# tester.net
KiCad netlist of a schematic drawn in EAGLE
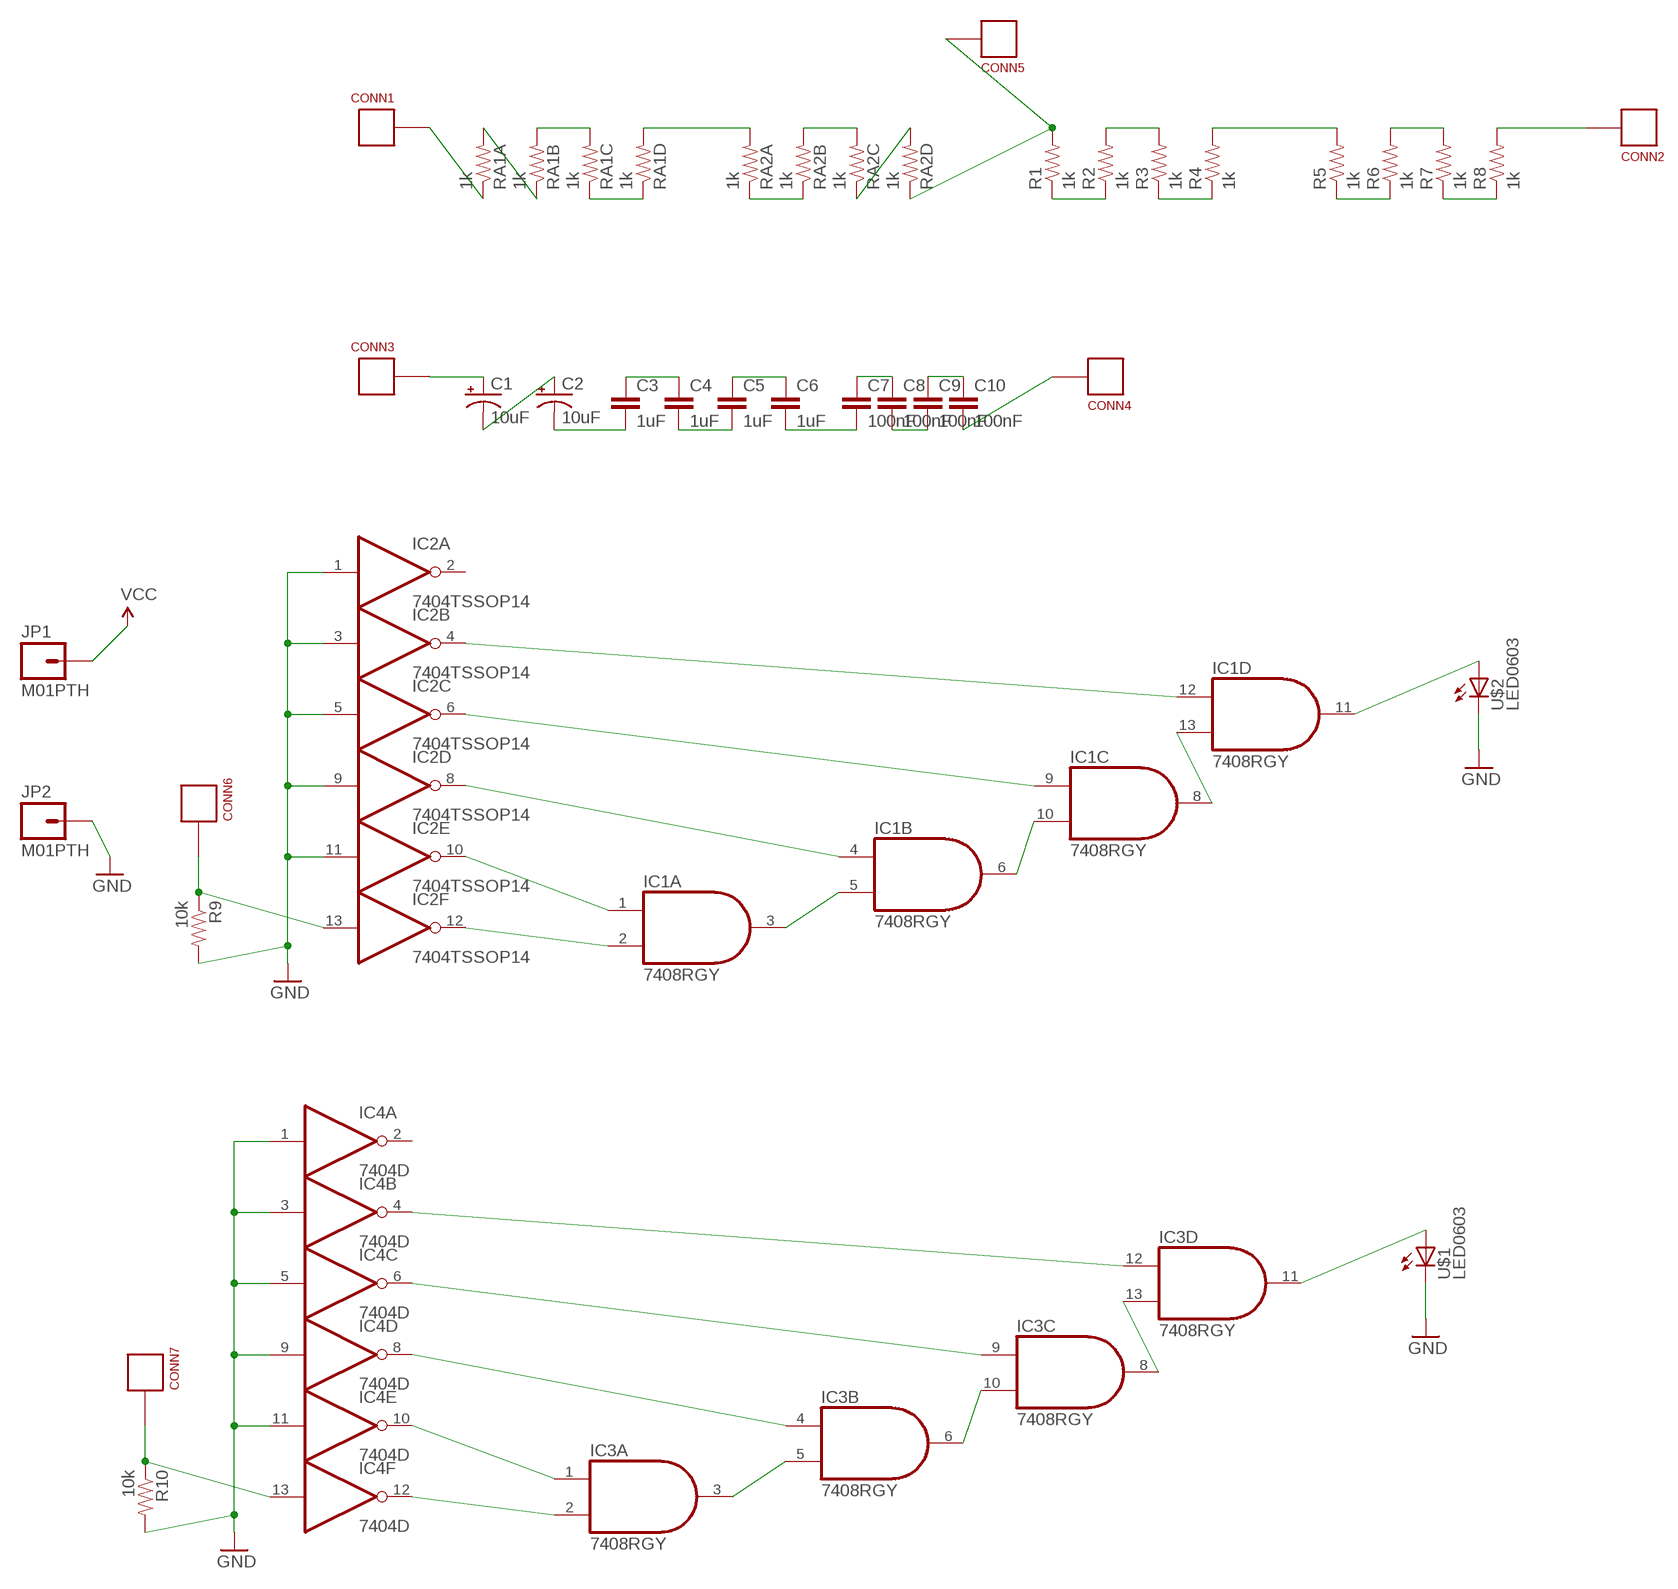
[diagram p0: schematic, sheet 1]

(export (version "E")
  (design (tool "Eeschema 10.0.6"))
  (components
    (comp (ref "C1")
      (value "10uF")
      (footprint "eagle-import:EIA3216")
      (libsource (lib "eagle-import") (part "CAP_POL1206"))
    )
    (comp (ref "C2")
      (value "10uF")
      (footprint "eagle-import:EIA3216")
      (libsource (lib "eagle-import") (part "CAP_POL1206"))
    )
    (comp (ref "C3")
      (value "1uF")
      (footprint "eagle-import:0805")
      (libsource (lib "eagle-import") (part "CAP0805"))
    )
    (comp (ref "C4")
      (value "1uF")
      (footprint "eagle-import:0805")
      (libsource (lib "eagle-import") (part "CAP0805"))
    )
    (comp (ref "C5")
      (value "1uF")
      (footprint "eagle-import:0805")
      (libsource (lib "eagle-import") (part "CAP0805"))
    )
    (comp (ref "C6")
      (value "1uF")
      (footprint "eagle-import:0805")
      (libsource (lib "eagle-import") (part "CAP0805"))
    )
    (comp (ref "C7")
      (value "100nF")
      (footprint "eagle-import:0402-CAP")
      (libsource (lib "eagle-import") (part "CAP0402-CAP"))
    )
    (comp (ref "C8")
      (value "100nF")
      (footprint "eagle-import:0402-CAP")
      (libsource (lib "eagle-import") (part "CAP0402-CAP"))
    )
    (comp (ref "C9")
      (value "100nF")
      (footprint "eagle-import:0402-CAP")
      (libsource (lib "eagle-import") (part "CAP0402-CAP"))
    )
    (comp (ref "C10")
      (value "100nF")
      (footprint "eagle-import:0402-CAP")
      (libsource (lib "eagle-import") (part "CAP0402-CAP"))
    )
    (comp (ref "CONN1")
      (value "CONNECTOR")
      (footprint "eagle-import:TESTPAD")
      (libsource (lib "eagle-import") (part "CONNECTOR"))
    )
    (comp (ref "CONN2")
      (value "CONNECTOR")
      (footprint "eagle-import:TESTPAD")
      (libsource (lib "eagle-import") (part "CONNECTOR"))
    )
    (comp (ref "CONN3")
      (value "CONNECTOR")
      (footprint "eagle-import:TESTPAD")
      (libsource (lib "eagle-import") (part "CONNECTOR"))
    )
    (comp (ref "CONN4")
      (value "CONNECTOR")
      (footprint "eagle-import:TESTPAD")
      (libsource (lib "eagle-import") (part "CONNECTOR"))
    )
    (comp (ref "CONN5")
      (value "CONNECTOR")
      (footprint "eagle-import:TESTPAD")
      (libsource (lib "eagle-import") (part "CONNECTOR"))
    )
    (comp (ref "CONN6")
      (value "CONNECTOR")
      (footprint "eagle-import:TESTPAD")
      (libsource (lib "eagle-import") (part "CONNECTOR"))
    )
    (comp (ref "CONN7")
      (value "CONNECTOR")
      (footprint "eagle-import:TESTPAD")
      (libsource (lib "eagle-import") (part "CONNECTOR"))
    )
    (comp (ref "IC1")
      (value "7408RGY")
      (footprint "eagle-import:QFN14")
      (libsource (lib "eagle-import") (part "7408RGY"))
    )
    (comp (ref "IC2")
      (value "7404TSSOP14")
      (footprint "eagle-import:TSSOP14")
      (libsource (lib "eagle-import") (part "7404TSSOP14"))
    )
    (comp (ref "IC3")
      (value "7408RGY")
      (footprint "eagle-import:QFN14")
      (libsource (lib "eagle-import") (part "7408RGY"))
    )
    (comp (ref "IC4")
      (value "7404D")
      (footprint "eagle-import:SO14")
      (libsource (lib "eagle-import") (part "7404D"))
    )
    (comp (ref "JP1")
      (value "M01PTH")
      (footprint "eagle-import:1X01")
      (libsource (lib "eagle-import") (part "M01PTH"))
    )
    (comp (ref "JP2")
      (value "M01PTH")
      (footprint "eagle-import:1X01")
      (libsource (lib "eagle-import") (part "M01PTH"))
    )
    (comp (ref "R1")
      (value "1k")
      (footprint "eagle-import:0603-RES")
      (libsource (lib "eagle-import") (part "RESISTOR0603"))
    )
    (comp (ref "R2")
      (value "1k")
      (footprint "eagle-import:0603-RES")
      (libsource (lib "eagle-import") (part "RESISTOR0603"))
    )
    (comp (ref "R3")
      (value "1k")
      (footprint "eagle-import:0603-RES")
      (libsource (lib "eagle-import") (part "RESISTOR0603"))
    )
    (comp (ref "R4")
      (value "1k")
      (footprint "eagle-import:0603-RES")
      (libsource (lib "eagle-import") (part "RESISTOR0603"))
    )
    (comp (ref "R5")
      (value "1k")
      (footprint "eagle-import:0402-RES")
      (libsource (lib "eagle-import") (part "RESISTOR0402"))
    )
    (comp (ref "R6")
      (value "1k")
      (footprint "eagle-import:0402-RES")
      (libsource (lib "eagle-import") (part "RESISTOR0402"))
    )
    (comp (ref "R7")
      (value "1k")
      (footprint "eagle-import:0402-RES")
      (libsource (lib "eagle-import") (part "RESISTOR0402"))
    )
    (comp (ref "R8")
      (value "1k")
      (footprint "eagle-import:0402-RES")
      (libsource (lib "eagle-import") (part "RESISTOR0402"))
    )
    (comp (ref "R9")
      (value "10k")
      (footprint "eagle-import:0402-RES")
      (libsource (lib "eagle-import") (part "RESISTOR0402"))
    )
    (comp (ref "R10")
      (value "10k")
      (footprint "eagle-import:0402-RES")
      (libsource (lib "eagle-import") (part "RESISTOR0402"))
    )
    (comp (ref "RA1")
      (value "1k")
      (footprint "eagle-import:0603-ARV")
      (libsource (lib "eagle-import") (part "RESISTOR_ARRAY0603_X4"))
    )
    (comp (ref "RA2")
      (value "1k")
      (footprint "eagle-import:0603-ARV")
      (libsource (lib "eagle-import") (part "RESISTOR_ARRAY0603_X4"))
    )
    (comp (ref "U$1")
      (value "LED0603")
      (footprint "eagle-import:0603_LED")
      (libsource (lib "eagle-import") (part "LED0603"))
    )
    (comp (ref "U$2")
      (value "LED0603")
      (footprint "eagle-import:0603_LED")
      (libsource (lib "eagle-import") (part "LED0603"))
    )
  )
  (nets
    (net (code "1") (name "GND") (class "Default")
      (node (ref "IC2") (pin "1") (pinfunction "I_1") (pintype "input"))
      (node (ref "IC2") (pin "11") (pinfunction "I_11") (pintype "input"))
      (node (ref "IC2") (pin "3") (pinfunction "I_3") (pintype "input"))
      (node (ref "IC2") (pin "5") (pinfunction "I_5") (pintype "input"))
      (node (ref "IC2") (pin "9") (pinfunction "I_9") (pintype "input"))
      (node (ref "IC4") (pin "1") (pinfunction "I_1") (pintype "input"))
      (node (ref "IC4") (pin "11") (pinfunction "I_11") (pintype "input"))
      (node (ref "IC4") (pin "3") (pinfunction "I_3") (pintype "input"))
      (node (ref "IC4") (pin "5") (pinfunction "I_5") (pintype "input"))
      (node (ref "IC4") (pin "9") (pinfunction "I_9") (pintype "input"))
      (node (ref "JP2") (pin "1") (pinfunction "1_1") (pintype "passive"))
      (node (ref "R10") (pin "2") (pinfunction "2_2") (pintype "passive"))
      (node (ref "R9") (pin "2") (pinfunction "2_2") (pintype "passive"))
      (node (ref "U$1") (pin "C") (pinfunction "C_C") (pintype "passive"))
      (node (ref "U$2") (pin "C") (pinfunction "C_C") (pintype "passive"))
    )
    (net (code "2") (name "Net-(C1-+)") (class "Default")
      (node (ref "C1") (pin "A") (pinfunction "+_A") (pintype "passive"))
      (node (ref "CONN3") (pin "P") (pinfunction "P_P") (pintype "bidirectional"))
    )
    (net (code "3") (name "Net-(C1--)") (class "Default")
      (node (ref "C1") (pin "C") (pinfunction "-_C") (pintype "passive"))
      (node (ref "C2") (pin "A") (pinfunction "+_A") (pintype "passive"))
    )
    (net (code "4") (name "Net-(C2--)") (class "Default")
      (node (ref "C2") (pin "C") (pinfunction "-_C") (pintype "passive"))
      (node (ref "C3") (pin "2") (pinfunction "2_2") (pintype "passive"))
    )
    (net (code "5") (name "Net-(C3-Pad1)") (class "Default")
      (node (ref "C3") (pin "1") (pinfunction "1_1") (pintype "passive"))
      (node (ref "C4") (pin "1") (pinfunction "1_1") (pintype "passive"))
    )
    (net (code "6") (name "Net-(C4-Pad2)") (class "Default")
      (node (ref "C4") (pin "2") (pinfunction "2_2") (pintype "passive"))
      (node (ref "C5") (pin "2") (pinfunction "2_2") (pintype "passive"))
    )
    (net (code "7") (name "Net-(C5-Pad1)") (class "Default")
      (node (ref "C5") (pin "1") (pinfunction "1_1") (pintype "passive"))
      (node (ref "C6") (pin "1") (pinfunction "1_1") (pintype "passive"))
    )
    (net (code "8") (name "Net-(C6-Pad2)") (class "Default")
      (node (ref "C6") (pin "2") (pinfunction "2_2") (pintype "passive"))
      (node (ref "C7") (pin "2") (pinfunction "2_2") (pintype "passive"))
    )
    (net (code "9") (name "Net-(C7-Pad1)") (class "Default")
      (node (ref "C7") (pin "1") (pinfunction "1_1") (pintype "passive"))
      (node (ref "C8") (pin "1") (pinfunction "1_1") (pintype "passive"))
    )
    (net (code "10") (name "Net-(C8-Pad2)") (class "Default")
      (node (ref "C8") (pin "2") (pinfunction "2_2") (pintype "passive"))
      (node (ref "C9") (pin "2") (pinfunction "2_2") (pintype "passive"))
    )
    (net (code "11") (name "Net-(C10-Pad1)") (class "Default")
      (node (ref "C10") (pin "1") (pinfunction "1_1") (pintype "passive"))
      (node (ref "C9") (pin "1") (pinfunction "1_1") (pintype "passive"))
    )
    (net (code "12") (name "Net-(C10-Pad2)") (class "Default")
      (node (ref "C10") (pin "2") (pinfunction "2_2") (pintype "passive"))
      (node (ref "CONN4") (pin "P") (pinfunction "P_P") (pintype "bidirectional"))
    )
    (net (code "13") (name "Net-(CONN1-PadP)") (class "Default")
      (node (ref "CONN1") (pin "P") (pinfunction "P_P") (pintype "bidirectional"))
      (node (ref "RA1") (pin "1") (pinfunction "1_1") (pintype "passive"))
    )
    (net (code "14") (name "Net-(CONN2-PadP)") (class "Default")
      (node (ref "CONN2") (pin "P") (pinfunction "P_P") (pintype "bidirectional"))
      (node (ref "R8") (pin "2") (pinfunction "2_2") (pintype "passive"))
    )
    (net (code "15") (name "Net-(IC1A-I0)") (class "Default")
      (node (ref "IC1") (pin "1") (pinfunction "I0_1") (pintype "input"))
      (node (ref "IC2") (pin "10") (pinfunction "O_10") (pintype "output"))
    )
    (net (code "16") (name "Net-(IC1A-I1)") (class "Default")
      (node (ref "IC1") (pin "2") (pinfunction "I1_2") (pintype "input"))
      (node (ref "IC2") (pin "12") (pinfunction "O_12") (pintype "output"))
    )
    (net (code "17") (name "Net-(IC1A-O)") (class "Default")
      (node (ref "IC1") (pin "3") (pinfunction "O_3") (pintype "output"))
      (node (ref "IC1") (pin "5") (pinfunction "I1_5") (pintype "input"))
    )
    (net (code "18") (name "Net-(IC1B-I0)") (class "Default")
      (node (ref "IC1") (pin "4") (pinfunction "I0_4") (pintype "input"))
      (node (ref "IC2") (pin "8") (pinfunction "O_8") (pintype "output"))
    )
    (net (code "19") (name "Net-(IC1B-O)") (class "Default")
      (node (ref "IC1") (pin "10") (pinfunction "I1_10") (pintype "input"))
      (node (ref "IC1") (pin "6") (pinfunction "O_6") (pintype "output"))
    )
    (net (code "20") (name "Net-(IC1C-I0)") (class "Default")
      (node (ref "IC1") (pin "9") (pinfunction "I0_9") (pintype "input"))
      (node (ref "IC2") (pin "6") (pinfunction "O_6") (pintype "output"))
    )
    (net (code "21") (name "Net-(IC1C-O)") (class "Default")
      (node (ref "IC1") (pin "13") (pinfunction "I1_13") (pintype "input"))
      (node (ref "IC1") (pin "8") (pinfunction "O_8") (pintype "output"))
    )
    (net (code "22") (name "Net-(IC1D-I0)") (class "Default")
      (node (ref "IC1") (pin "12") (pinfunction "I0_12") (pintype "input"))
      (node (ref "IC2") (pin "4") (pinfunction "O_4") (pintype "output"))
    )
    (net (code "23") (name "Net-(IC1D-O)") (class "Default")
      (node (ref "IC1") (pin "11") (pinfunction "O_11") (pintype "output"))
      (node (ref "U$2") (pin "A") (pinfunction "A_A") (pintype "passive"))
    )
    (net (code "24") (name "Net-(IC2F-I)") (class "Default")
      (node (ref "CONN6") (pin "P") (pinfunction "P_P") (pintype "bidirectional"))
      (node (ref "IC2") (pin "13") (pinfunction "I_13") (pintype "input"))
      (node (ref "R9") (pin "1") (pinfunction "1_1") (pintype "passive"))
    )
    (net (code "25") (name "Net-(IC3A-I0)") (class "Default")
      (node (ref "IC3") (pin "1") (pinfunction "I0_1") (pintype "input"))
      (node (ref "IC4") (pin "10") (pinfunction "O_10") (pintype "output"))
    )
    (net (code "26") (name "Net-(IC3A-I1)") (class "Default")
      (node (ref "IC3") (pin "2") (pinfunction "I1_2") (pintype "input"))
      (node (ref "IC4") (pin "12") (pinfunction "O_12") (pintype "output"))
    )
    (net (code "27") (name "Net-(IC3A-O)") (class "Default")
      (node (ref "IC3") (pin "3") (pinfunction "O_3") (pintype "output"))
      (node (ref "IC3") (pin "5") (pinfunction "I1_5") (pintype "input"))
    )
    (net (code "28") (name "Net-(IC3B-I0)") (class "Default")
      (node (ref "IC3") (pin "4") (pinfunction "I0_4") (pintype "input"))
      (node (ref "IC4") (pin "8") (pinfunction "O_8") (pintype "output"))
    )
    (net (code "29") (name "Net-(IC3B-O)") (class "Default")
      (node (ref "IC3") (pin "10") (pinfunction "I1_10") (pintype "input"))
      (node (ref "IC3") (pin "6") (pinfunction "O_6") (pintype "output"))
    )
    (net (code "30") (name "Net-(IC3C-I0)") (class "Default")
      (node (ref "IC3") (pin "9") (pinfunction "I0_9") (pintype "input"))
      (node (ref "IC4") (pin "6") (pinfunction "O_6") (pintype "output"))
    )
    (net (code "31") (name "Net-(IC3C-O)") (class "Default")
      (node (ref "IC3") (pin "13") (pinfunction "I1_13") (pintype "input"))
      (node (ref "IC3") (pin "8") (pinfunction "O_8") (pintype "output"))
    )
    (net (code "32") (name "Net-(IC3D-I0)") (class "Default")
      (node (ref "IC3") (pin "12") (pinfunction "I0_12") (pintype "input"))
      (node (ref "IC4") (pin "4") (pinfunction "O_4") (pintype "output"))
    )
    (net (code "33") (name "Net-(IC3D-O)") (class "Default")
      (node (ref "IC3") (pin "11") (pinfunction "O_11") (pintype "output"))
      (node (ref "U$1") (pin "A") (pinfunction "A_A") (pintype "passive"))
    )
    (net (code "34") (name "Net-(IC4F-I)") (class "Default")
      (node (ref "CONN7") (pin "P") (pinfunction "P_P") (pintype "bidirectional"))
      (node (ref "IC4") (pin "13") (pinfunction "I_13") (pintype "input"))
      (node (ref "R10") (pin "1") (pinfunction "1_1") (pintype "passive"))
    )
    (net (code "35") (name "Net-(R1-Pad1)") (class "Default")
      (node (ref "R1") (pin "1") (pinfunction "1_1") (pintype "passive"))
      (node (ref "R2") (pin "1") (pinfunction "1_1") (pintype "passive"))
    )
    (net (code "36") (name "Net-(R2-Pad2)") (class "Default")
      (node (ref "R2") (pin "2") (pinfunction "2_2") (pintype "passive"))
      (node (ref "R3") (pin "2") (pinfunction "2_2") (pintype "passive"))
    )
    (net (code "37") (name "Net-(R3-Pad1)") (class "Default")
      (node (ref "R3") (pin "1") (pinfunction "1_1") (pintype "passive"))
      (node (ref "R4") (pin "1") (pinfunction "1_1") (pintype "passive"))
    )
    (net (code "38") (name "Net-(R4-Pad2)") (class "Default")
      (node (ref "R4") (pin "2") (pinfunction "2_2") (pintype "passive"))
      (node (ref "R5") (pin "2") (pinfunction "2_2") (pintype "passive"))
    )
    (net (code "39") (name "Net-(R5-Pad1)") (class "Default")
      (node (ref "R5") (pin "1") (pinfunction "1_1") (pintype "passive"))
      (node (ref "R6") (pin "1") (pinfunction "1_1") (pintype "passive"))
    )
    (net (code "40") (name "Net-(R6-Pad2)") (class "Default")
      (node (ref "R6") (pin "2") (pinfunction "2_2") (pintype "passive"))
      (node (ref "R7") (pin "2") (pinfunction "2_2") (pintype "passive"))
    )
    (net (code "41") (name "Net-(R7-Pad1)") (class "Default")
      (node (ref "R7") (pin "1") (pinfunction "1_1") (pintype "passive"))
      (node (ref "R8") (pin "1") (pinfunction "1_1") (pintype "passive"))
    )
    (net (code "42") (name "Net-(RA1A-2)") (class "Default")
      (node (ref "RA1") (pin "2") (pinfunction "1_2") (pintype "passive"))
      (node (ref "RA1") (pin "8") (pinfunction "2_8") (pintype "passive"))
    )
    (net (code "43") (name "Net-(RA1B-2)") (class "Default")
      (node (ref "RA1") (pin "6") (pinfunction "2_6") (pintype "passive"))
      (node (ref "RA1") (pin "7") (pinfunction "2_7") (pintype "passive"))
    )
    (net (code "44") (name "Net-(RA1C-1)") (class "Default")
      (node (ref "RA1") (pin "3") (pinfunction "1_3") (pintype "passive"))
      (node (ref "RA1") (pin "4") (pinfunction "1_4") (pintype "passive"))
    )
    (net (code "45") (name "Net-(RA1D-2)") (class "Default")
      (node (ref "RA1") (pin "5") (pinfunction "2_5") (pintype "passive"))
      (node (ref "RA2") (pin "8") (pinfunction "2_8") (pintype "passive"))
    )
    (net (code "46") (name "Net-(RA2B-1)") (class "Default")
      (node (ref "RA2") (pin "1") (pinfunction "1_1") (pintype "passive"))
      (node (ref "RA2") (pin "2") (pinfunction "1_2") (pintype "passive"))
    )
    (net (code "47") (name "Net-(RA2B-2)") (class "Default")
      (node (ref "RA2") (pin "6") (pinfunction "2_6") (pintype "passive"))
      (node (ref "RA2") (pin "7") (pinfunction "2_7") (pintype "passive"))
    )
    (net (code "48") (name "Net-(RA2C-1)") (class "Default")
      (node (ref "RA2") (pin "3") (pinfunction "1_3") (pintype "passive"))
      (node (ref "RA2") (pin "5") (pinfunction "2_5") (pintype "passive"))
    )
    (net (code "49") (name "Net-(RA2D-1)") (class "Default")
      (node (ref "CONN5") (pin "P") (pinfunction "P_P") (pintype "bidirectional"))
      (node (ref "R1") (pin "2") (pinfunction "2_2") (pintype "passive"))
      (node (ref "RA2") (pin "4") (pinfunction "1_4") (pintype "passive"))
    )
    (net (code "50") (name "VCC") (class "Default")
      (node (ref "JP1") (pin "1") (pinfunction "1_1") (pintype "passive"))
    )
    (net (code "51") (name "unconnected-(IC2A-O-Pad2)") (class "Default")
      (node (ref "IC2") (pin "2") (pinfunction "O_2") (pintype "output"))
    )
    (net (code "52") (name "unconnected-(IC4A-O-Pad2)") (class "Default")
      (node (ref "IC4") (pin "2") (pinfunction "O_2") (pintype "output"))
    )
  )
)
